# SparkFun_Dev_ESP32_C3_MINI.net
KiCad netlist of a schematic drawn in EAGLE
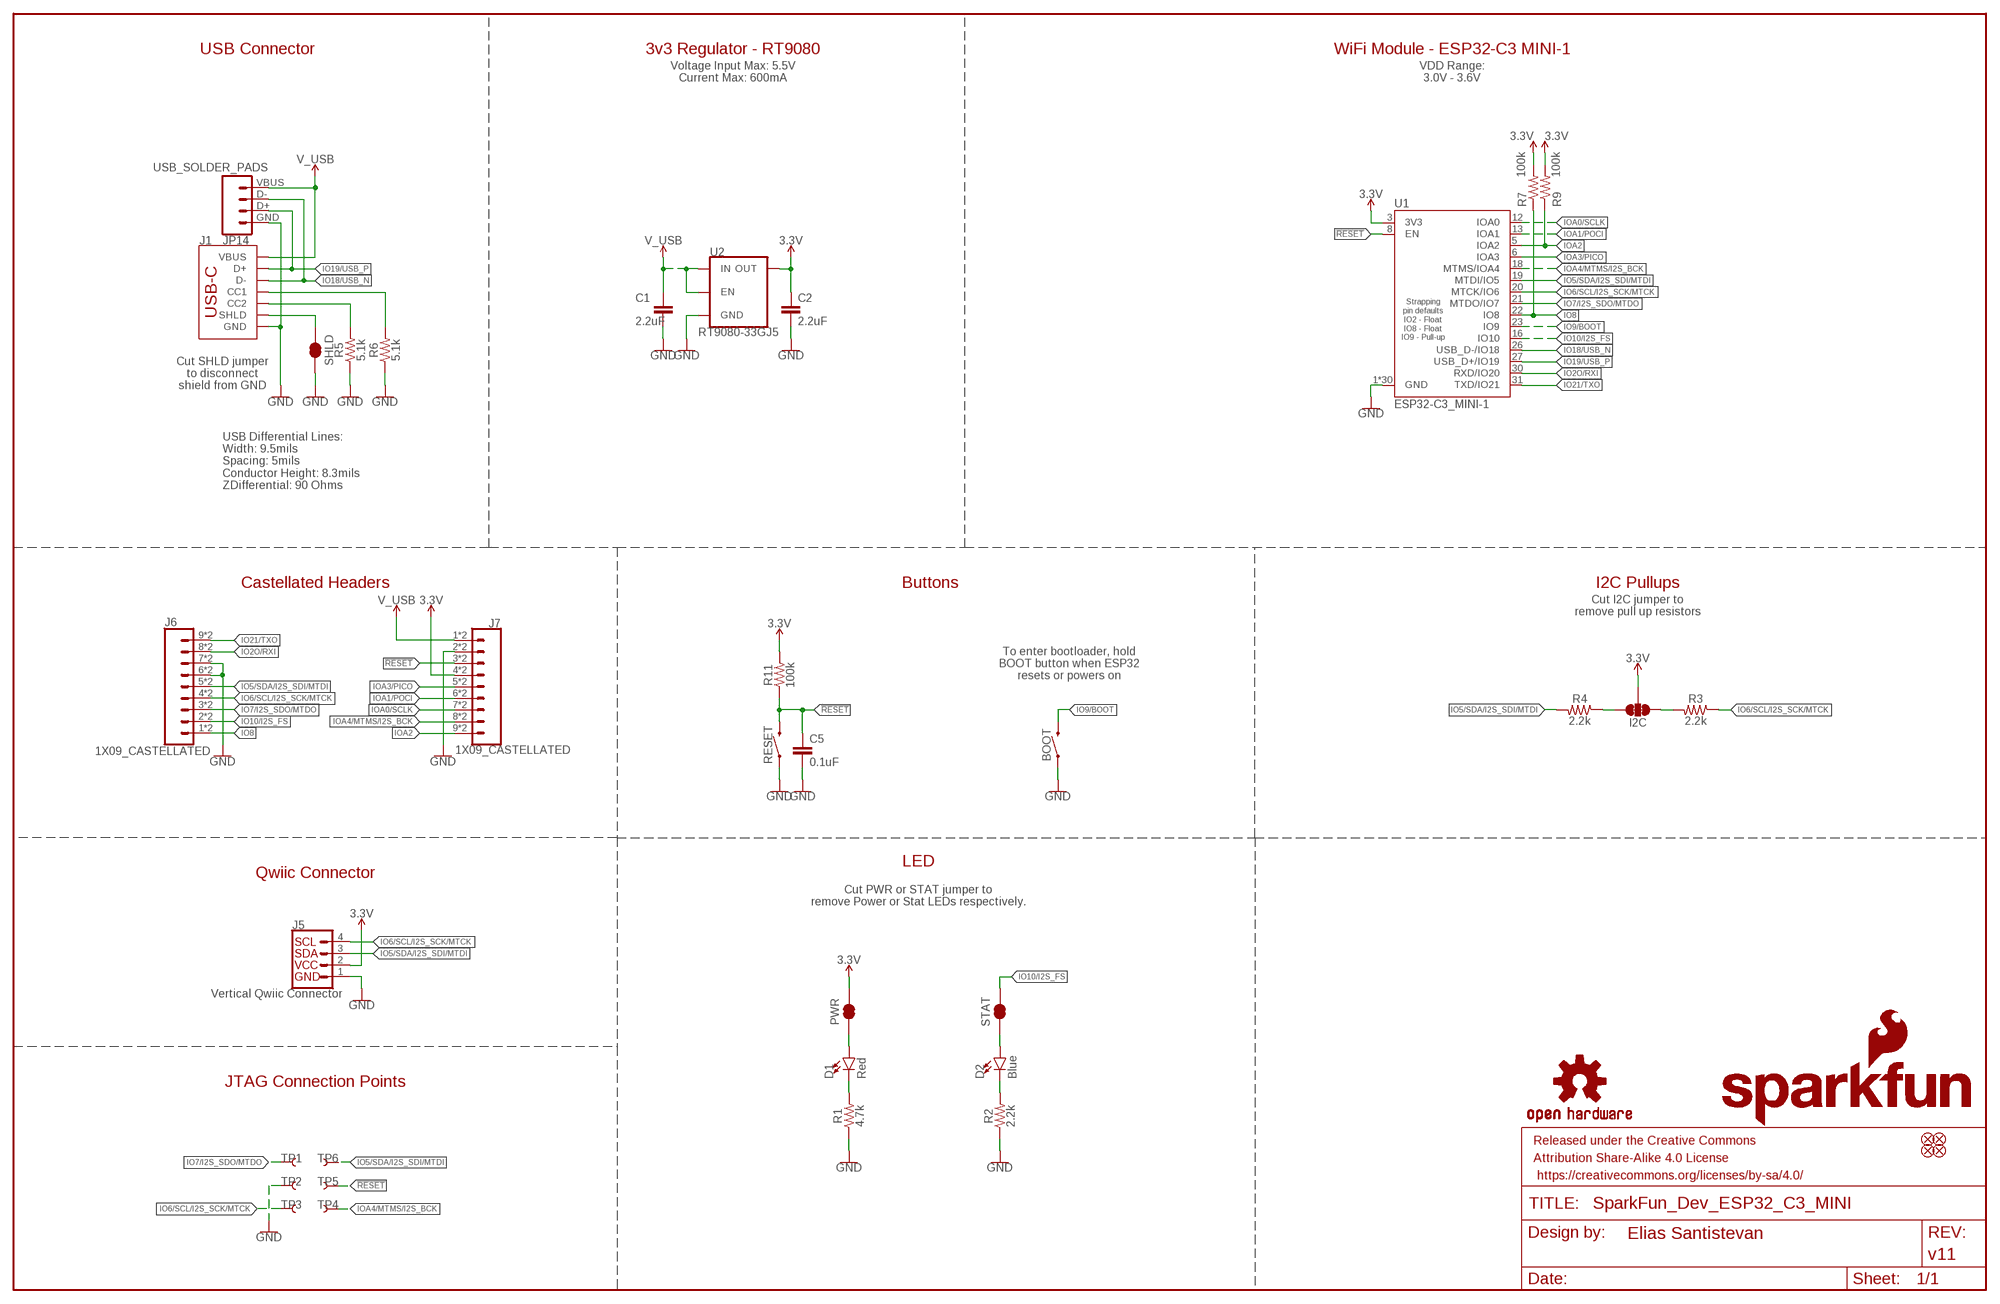
[diagram p0: schematic, sheet 1]

(export (version "E")
  (design (tool "Eeschema 10.0.6"))
  (components
    (comp (ref "BOOT")
      (value "MOMENTARY-SWITCH-SPST-SMD-4.6X2.8MM")
      (footprint "eagle-import:TACTILE_SWITCH_SMD_4.6X2.8MM")
      (libsource (lib "eagle-import") (part "MOMENTARY-SWITCH-SPST-SMD-4.6X2.8MM"))
    )
    (comp (ref "C1")
      (value "2.2uF")
      (footprint "eagle-import:0402-TIGHT")
      (libsource (lib "eagle-import") (part "2.2UF-0402_TIGHT-10V-10%-X5R"))
    )
    (comp (ref "C2")
      (value "2.2uF")
      (footprint "eagle-import:0402-TIGHT")
      (libsource (lib "eagle-import") (part "2.2UF-0402_TIGHT-10V-10%-X5R"))
    )
    (comp (ref "C5")
      (value "0.1uF")
      (footprint "eagle-import:0402-TIGHT")
      (libsource (lib "eagle-import") (part "0.1UF-0402T-6.3V-10%-X7R"))
    )
    (comp (ref "D1")
      (value "Red")
      (footprint "eagle-import:LED-0603")
      (libsource (lib "eagle-import") (part "LED-RED_0603-KB"))
    )
    (comp (ref "D2")
      (value "Blue")
      (footprint "eagle-import:LED-0603")
      (libsource (lib "eagle-import") (part "LED-BLUE0603"))
    )
    (comp (ref "FD1")
      (value "FIDUCIALUFIDUCIAL")
      (footprint "eagle-import:FIDUCIAL-MICRO")
      (libsource (lib "eagle-import") (part "FIDUCIALUFIDUCIAL"))
    )
    (comp (ref "FD2")
      (value "FIDUCIALUFIDUCIAL")
      (footprint "eagle-import:FIDUCIAL-MICRO")
      (libsource (lib "eagle-import") (part "FIDUCIALUFIDUCIAL"))
    )
    (comp (ref "FD3")
      (value "FIDUCIALUFIDUCIAL")
      (footprint "eagle-import:FIDUCIAL-MICRO")
      (libsource (lib "eagle-import") (part "FIDUCIALUFIDUCIAL"))
    )
    (comp (ref "FD4")
      (value "FIDUCIALUFIDUCIAL")
      (footprint "eagle-import:FIDUCIAL-MICRO")
      (libsource (lib "eagle-import") (part "FIDUCIALUFIDUCIAL"))
    )
    (comp (ref "FRAME2")
      (value "FRAME-LEDGER")
      (footprint "eagle-import:CREATIVE_COMMONS")
      (fields (field (name "DESIGNER") "Elias Santistevan") (field (name "REV") "v11"))
      (libsource (lib "eagle-import") (part "FRAME-LEDGER"))
    )
    (comp (ref "I2C")
      (value "JUMPER-SMT_3_2-NC_TRACE_SILK")
      (footprint "eagle-import:SMT-JUMPER_3_2-NC_TRACE_SILK")
      (libsource (lib "eagle-import") (part "JUMPER-SMT_3_2-NC_TRACE_SILK"))
    )
    (comp (ref "J1")
      (value "USB Female Type C Connector")
      (footprint "eagle-import:USB-C-16P_4LAYER-PADS")
      (libsource (lib "eagle-import") (part "USB_C_4-LAYER_PADS"))
    )
    (comp (ref "J5")
      (value "Vertical Qwiic Connector")
      (footprint "eagle-import:JST04_1MM_VERT")
      (libsource (lib "eagle-import") (part "QWIIC_CONNECTOR"))
    )
    (comp (ref "J6")
      (value "1X09_CASTELLATED")
      (footprint "eagle-import:1X09_CASTELLATED")
      (libsource (lib "eagle-import") (part "1X09_CASTELLATED"))
    )
    (comp (ref "J7")
      (value "1X09_CASTELLATED")
      (footprint "eagle-import:1X09_CASTELLATED")
      (libsource (lib "eagle-import") (part "1X09_CASTELLATED"))
    )
    (comp (ref "JP14")
      (value "USB_SOLDER_PADS")
      (footprint "eagle-import:USB-SOLDER-PADS")
      (libsource (lib "eagle-import") (part "USB_SOLDER_PADS"))
    )
    (comp (ref "LOGO1")
      (value "SFE_LOGO_NAME_FLAMEBLANK")
      (footprint "eagle-import:BLANK")
      (libsource (lib "eagle-import") (part "SFE_LOGO_NAME_FLAMEBLANK"))
    )
    (comp (ref "LOGO3")
      (value "OSHW-LOGOS")
      (footprint "eagle-import:OSHW-LOGO-S")
      (libsource (lib "eagle-import") (part "OSHW-LOGOS"))
    )
    (comp (ref "PWR")
      (value "JUMPER-SMT_2_NC_TRACE_SILK")
      (footprint "eagle-import:SMT-JUMPER_2_NC_TRACE_SILK")
      (libsource (lib "eagle-import") (part "JUMPER-SMT_2_NC_TRACE_SILK"))
    )
    (comp (ref "R1")
      (value "4.7k")
      (footprint "eagle-import:0402-TIGHT")
      (libsource (lib "eagle-import") (part "4.7KOHM-0402T-1/16W-1%"))
    )
    (comp (ref "R2")
      (value "2.2k")
      (footprint "eagle-import:0402-TIGHT")
      (libsource (lib "eagle-import") (part "2.2KOHM-0402T-1/16W-1%"))
    )
    (comp (ref "R3")
      (value "2.2k")
      (footprint "eagle-import:0402-TIGHT")
      (libsource (lib "eagle-import") (part "2.2KOHM-0402T-1/16W-1%"))
    )
    (comp (ref "R4")
      (value "2.2k")
      (footprint "eagle-import:0402-TIGHT")
      (libsource (lib "eagle-import") (part "2.2KOHM-0402T-1/16W-1%"))
    )
    (comp (ref "R5")
      (value "5.1k")
      (footprint "eagle-import:0402-TIGHT")
      (libsource (lib "eagle-import") (part "5.1KOHM-0402T-1/16W-1%"))
    )
    (comp (ref "R6")
      (value "5.1k")
      (footprint "eagle-import:0402-TIGHT")
      (libsource (lib "eagle-import") (part "5.1KOHM-0402T-1/16W-1%"))
    )
    (comp (ref "R7")
      (value "100k")
      (footprint "eagle-import:0402-TIGHT")
      (libsource (lib "eagle-import") (part "100KOHM-0402T-1/16W-1%"))
    )
    (comp (ref "R9")
      (value "100k")
      (footprint "eagle-import:0402-TIGHT")
      (libsource (lib "eagle-import") (part "100KOHM-0402T-1/16W-1%"))
    )
    (comp (ref "R11")
      (value "100k")
      (footprint "eagle-import:0402-TIGHT")
      (libsource (lib "eagle-import") (part "100KOHM-0402T-1/16W-1%"))
    )
    (comp (ref "RESET")
      (value "MOMENTARY-SWITCH-SPST-SMD-4.6X2.8MM")
      (footprint "eagle-import:TACTILE_SWITCH_SMD_4.6X2.8MM")
      (libsource (lib "eagle-import") (part "MOMENTARY-SWITCH-SPST-SMD-4.6X2.8MM"))
    )
    (comp (ref "SHLD")
      (value "JUMPER-SMT_2_NC_TRACE_SILK")
      (footprint "eagle-import:SMT-JUMPER_2_NC_TRACE_SILK")
      (libsource (lib "eagle-import") (part "JUMPER-SMT_2_NC_TRACE_SILK"))
    )
    (comp (ref "STAT")
      (value "JUMPER-SMT_2_NC_TRACE_SILK")
      (footprint "eagle-import:SMT-JUMPER_2_NC_TRACE_SILK")
      (libsource (lib "eagle-import") (part "JUMPER-SMT_2_NC_TRACE_SILK"))
    )
    (comp (ref "TP1")
      (value "TEST-POINT3X5")
      (footprint "eagle-import:PAD.03X.05")
      (libsource (lib "eagle-import") (part "TEST-POINT3X5"))
    )
    (comp (ref "TP2")
      (value "TEST-POINT3X5")
      (footprint "eagle-import:PAD.03X.05")
      (libsource (lib "eagle-import") (part "TEST-POINT3X5"))
    )
    (comp (ref "TP3")
      (value "TEST-POINT3X5")
      (footprint "eagle-import:PAD.03X.05")
      (libsource (lib "eagle-import") (part "TEST-POINT3X5"))
    )
    (comp (ref "TP4")
      (value "TEST-POINT3X5")
      (footprint "eagle-import:PAD.03X.05")
      (libsource (lib "eagle-import") (part "TEST-POINT3X5"))
    )
    (comp (ref "TP5")
      (value "TEST-POINT3X5")
      (footprint "eagle-import:PAD.03X.05")
      (libsource (lib "eagle-import") (part "TEST-POINT3X5"))
    )
    (comp (ref "TP6")
      (value "TEST-POINT3X5")
      (footprint "eagle-import:PAD.03X.05")
      (libsource (lib "eagle-import") (part "TEST-POINT3X5"))
    )
    (comp (ref "U1")
      (value "ESP32-C3_MINI-1")
      (footprint "eagle-import:ESP32-C3-MINI-1")
      (libsource (lib "eagle-import") (part "ESP32-C3_MINI-1"))
    )
    (comp (ref "U2")
      (value "RT9080-33GJ5")
      (footprint "eagle-import:SOT23-5")
      (libsource (lib "eagle-import") (part "V_REG_RT9080"))
    )
  )
  (nets
    (net (code "1") (name "/~{RESET}") (class "Default")
      (node (ref "C5") (pin "1") (pinfunction "1_1") (pintype "passive"))
      (node (ref "J7") (pin "3") (pinfunction "3_3") (pintype "passive"))
      (node (ref "J7") (pin "3B") (pinfunction "3_3B") (pintype "passive"))
      (node (ref "R11") (pin "1") (pinfunction "1_1") (pintype "passive"))
      (node (ref "RESET") (pin "3") (pinfunction "2_3") (pintype "passive"))
      (node (ref "RESET") (pin "4") (pinfunction "2_4") (pintype "passive"))
      (node (ref "TP5") (pin "1") (pinfunction "1_1") (pintype "bidirectional"))
      (node (ref "U1") (pin "8") (pinfunction "EN_8") (pintype "bidirectional"))
    )
    (net (code "2") (name "3.3V") (class "Default")
      (node (ref "C2") (pin "1") (pinfunction "1_1") (pintype "passive"))
      (node (ref "I2C") (pin "2") (pinfunction "2_2") (pintype "passive"))
      (node (ref "J5") (pin "2") (pinfunction "2_2") (pintype "power_in"))
      (node (ref "J7") (pin "4") (pinfunction "4_4") (pintype "passive"))
      (node (ref "J7") (pin "4B") (pinfunction "4_4B") (pintype "passive"))
      (node (ref "PWR") (pin "2") (pinfunction "2_2") (pintype "passive"))
      (node (ref "R11") (pin "2") (pinfunction "2_2") (pintype "passive"))
      (node (ref "R7") (pin "2") (pinfunction "2_2") (pintype "passive"))
      (node (ref "R9") (pin "2") (pinfunction "2_2") (pintype "passive"))
      (node (ref "U1") (pin "3") (pinfunction "3V3_3") (pintype "bidirectional"))
      (node (ref "U2") (pin "5") (pinfunction "OUT_5") (pintype "passive"))
    )
    (net (code "3") (name "GND") (class "Default")
      (node (ref "BOOT") (pin "1") (pinfunction "1_1") (pintype "passive"))
      (node (ref "BOOT") (pin "2") (pinfunction "1_2") (pintype "passive"))
      (node (ref "C1") (pin "2") (pinfunction "2_2") (pintype "passive"))
      (node (ref "C2") (pin "2") (pinfunction "2_2") (pintype "passive"))
      (node (ref "C5") (pin "2") (pinfunction "2_2") (pintype "passive"))
      (node (ref "J1") (pin "GND") (pinfunction "GND_GND") (pintype "bidirectional"))
      (node (ref "J1") (pin "GND2") (pinfunction "GND_GND2") (pintype "bidirectional"))
      (node (ref "J5") (pin "1") (pinfunction "1_1") (pintype "power_in"))
      (node (ref "J6") (pin "6") (pinfunction "6_6") (pintype "passive"))
      (node (ref "J6") (pin "6B") (pinfunction "6_6B") (pintype "passive"))
      (node (ref "J6") (pin "7") (pinfunction "7_7") (pintype "passive"))
      (node (ref "J6") (pin "7B") (pinfunction "7_7B") (pintype "passive"))
      (node (ref "J7") (pin "2") (pinfunction "2_2") (pintype "passive"))
      (node (ref "J7") (pin "2B") (pinfunction "2_2B") (pintype "passive"))
      (node (ref "JP14") (pin "GND") (pinfunction "4_GND") (pintype "passive"))
      (node (ref "R1") (pin "1") (pinfunction "1_1") (pintype "passive"))
      (node (ref "R2") (pin "1") (pinfunction "1_1") (pintype "passive"))
      (node (ref "R5") (pin "1") (pinfunction "1_1") (pintype "passive"))
      (node (ref "R6") (pin "1") (pinfunction "1_1") (pintype "passive"))
      (node (ref "RESET") (pin "1") (pinfunction "1_1") (pintype "passive"))
      (node (ref "RESET") (pin "2") (pinfunction "1_2") (pintype "passive"))
      (node (ref "SHLD") (pin "2") (pinfunction "2_2") (pintype "passive"))
      (node (ref "TP2") (pin "1") (pinfunction "1_1") (pintype "bidirectional"))
      (node (ref "U1") (pin "1") (pinfunction "GND_1") (pintype "bidirectional"))
      (node (ref "U1") (pin "11") (pinfunction "GND_11") (pintype "bidirectional"))
      (node (ref "U1") (pin "14") (pinfunction "GND_14") (pintype "bidirectional"))
      (node (ref "U1") (pin "2") (pinfunction "GND_2") (pintype "bidirectional"))
      (node (ref "U1") (pin "36") (pinfunction "GND_36") (pintype "bidirectional"))
      (node (ref "U1") (pin "37") (pinfunction "GND_37") (pintype "bidirectional"))
      (node (ref "U1") (pin "38") (pinfunction "GND_38") (pintype "bidirectional"))
      (node (ref "U1") (pin "39") (pinfunction "GND_39") (pintype "bidirectional"))
      (node (ref "U1") (pin "40") (pinfunction "GND_40") (pintype "bidirectional"))
      (node (ref "U1") (pin "41") (pinfunction "GND_41") (pintype "bidirectional"))
      (node (ref "U1") (pin "42") (pinfunction "GND_42") (pintype "bidirectional"))
      (node (ref "U1") (pin "43") (pinfunction "GND_43") (pintype "bidirectional"))
      (node (ref "U1") (pin "44") (pinfunction "GND_44") (pintype "bidirectional"))
      (node (ref "U1") (pin "45") (pinfunction "GND_45") (pintype "bidirectional"))
      (node (ref "U1") (pin "46") (pinfunction "GND_46") (pintype "bidirectional"))
      (node (ref "U1") (pin "47") (pinfunction "GND_47") (pintype "bidirectional"))
      (node (ref "U1") (pin "48") (pinfunction "GND_48") (pintype "bidirectional"))
      (node (ref "U1") (pin "49.1") (pinfunction "GND_49.1") (pintype "bidirectional"))
      (node (ref "U1") (pin "49.2") (pinfunction "GND_49.2") (pintype "bidirectional"))
      (node (ref "U1") (pin "49.3") (pinfunction "GND_49.3") (pintype "bidirectional"))
      (node (ref "U1") (pin "49.4") (pinfunction "GND_49.4") (pintype "bidirectional"))
      (node (ref "U1") (pin "49.5") (pinfunction "GND_49.5") (pintype "bidirectional"))
      (node (ref "U1") (pin "49.6") (pinfunction "GND_49.6") (pintype "bidirectional"))
      (node (ref "U1") (pin "49.7") (pinfunction "GND_49.7") (pintype "bidirectional"))
      (node (ref "U1") (pin "49.8") (pinfunction "GND_49.8") (pintype "bidirectional"))
      (node (ref "U1") (pin "49.9") (pinfunction "GND_49.9") (pintype "bidirectional"))
      (node (ref "U1") (pin "50") (pinfunction "GND_50") (pintype "bidirectional"))
      (node (ref "U1") (pin "51") (pinfunction "GND_51") (pintype "bidirectional"))
      (node (ref "U1") (pin "52") (pinfunction "GND_52") (pintype "bidirectional"))
      (node (ref "U1") (pin "53") (pinfunction "GND_53") (pintype "bidirectional"))
      (node (ref "U2") (pin "2") (pinfunction "GND_2") (pintype "input"))
    )
    (net (code "4") (name "IO2O{slash}RXI") (class "Default")
      (node (ref "J6") (pin "8") (pinfunction "8_8") (pintype "passive"))
      (node (ref "J6") (pin "8B") (pinfunction "8_8B") (pintype "passive"))
      (node (ref "U1") (pin "30") (pinfunction "RXD/IO20_30") (pintype "bidirectional"))
    )
    (net (code "5") (name "IO5{slash}SDA{slash}I2S_SDI{slash}MTDI") (class "Default")
      (node (ref "J5") (pin "3") (pinfunction "3_3") (pintype "passive"))
      (node (ref "J6") (pin "5") (pinfunction "5_5") (pintype "passive"))
      (node (ref "J6") (pin "5B") (pinfunction "5_5B") (pintype "passive"))
      (node (ref "R4") (pin "2") (pinfunction "2_2") (pintype "passive"))
      (node (ref "TP6") (pin "1") (pinfunction "1_1") (pintype "bidirectional"))
      (node (ref "U1") (pin "19") (pinfunction "MTDI/IO5_19") (pintype "bidirectional"))
    )
    (net (code "6") (name "IO6{slash}SCL{slash}I2S_SCK{slash}MTCK") (class "Default")
      (node (ref "J5") (pin "4") (pinfunction "4_4") (pintype "passive"))
      (node (ref "J6") (pin "4") (pinfunction "4_4") (pintype "passive"))
      (node (ref "J6") (pin "4B") (pinfunction "4_4B") (pintype "passive"))
      (node (ref "R3") (pin "1") (pinfunction "1_1") (pintype "passive"))
      (node (ref "TP3") (pin "1") (pinfunction "1_1") (pintype "bidirectional"))
      (node (ref "U1") (pin "20") (pinfunction "MTCK/IO6_20") (pintype "bidirectional"))
    )
    (net (code "7") (name "IO7{slash}I2S_SDO{slash}MTDO") (class "Default")
      (node (ref "J6") (pin "3") (pinfunction "3_3") (pintype "passive"))
      (node (ref "J6") (pin "3B") (pinfunction "3_3B") (pintype "passive"))
      (node (ref "TP1") (pin "1") (pinfunction "1_1") (pintype "bidirectional"))
      (node (ref "U1") (pin "21") (pinfunction "MTDO/IO7_21") (pintype "bidirectional"))
    )
    (net (code "8") (name "IO8") (class "Default")
      (node (ref "J6") (pin "1") (pinfunction "1_1") (pintype "passive"))
      (node (ref "J6") (pin "1B") (pinfunction "1_1B") (pintype "passive"))
      (node (ref "R7") (pin "1") (pinfunction "1_1") (pintype "passive"))
      (node (ref "U1") (pin "22") (pinfunction "IO8_22") (pintype "bidirectional"))
    )
    (net (code "9") (name "IO9{slash}BOOT") (class "Default")
      (node (ref "BOOT") (pin "3") (pinfunction "2_3") (pintype "passive"))
      (node (ref "BOOT") (pin "4") (pinfunction "2_4") (pintype "passive"))
      (node (ref "U1") (pin "23") (pinfunction "IO9_23") (pintype "bidirectional"))
    )
    (net (code "10") (name "IO10{slash}I2S_FS") (class "Default")
      (node (ref "J6") (pin "2") (pinfunction "2_2") (pintype "passive"))
      (node (ref "J6") (pin "2B") (pinfunction "2_2B") (pintype "passive"))
      (node (ref "STAT") (pin "2") (pinfunction "2_2") (pintype "passive"))
      (node (ref "U1") (pin "16") (pinfunction "IO10_16") (pintype "bidirectional"))
    )
    (net (code "11") (name "IO18{slash}USB_N") (class "Default")
      (node (ref "J1") (pin "A7") (pinfunction "D-_A7") (pintype "bidirectional"))
      (node (ref "J1") (pin "B7") (pinfunction "D-_B7") (pintype "bidirectional"))
      (node (ref "JP14") (pin "D-") (pinfunction "2_D-") (pintype "passive"))
      (node (ref "U1") (pin "26") (pinfunction "USB_D-/IO18_26") (pintype "bidirectional"))
    )
    (net (code "12") (name "IO19{slash}USB_P") (class "Default")
      (node (ref "J1") (pin "A6") (pinfunction "D+_A6") (pintype "bidirectional"))
      (node (ref "J1") (pin "B6") (pinfunction "D+_B6") (pintype "bidirectional"))
      (node (ref "JP14") (pin "D+") (pinfunction "3_D+") (pintype "passive"))
      (node (ref "U1") (pin "27") (pinfunction "USB_D+/IO19_27") (pintype "bidirectional"))
    )
    (net (code "13") (name "IO21{slash}TXO") (class "Default")
      (node (ref "J6") (pin "9") (pinfunction "9_9") (pintype "passive"))
      (node (ref "J6") (pin "9B") (pinfunction "9_9B") (pintype "passive"))
      (node (ref "U1") (pin "31") (pinfunction "TXD/IO21_31") (pintype "bidirectional"))
    )
    (net (code "14") (name "IOA0{slash}SCLK") (class "Default")
      (node (ref "J7") (pin "7") (pinfunction "7_7") (pintype "passive"))
      (node (ref "J7") (pin "7B") (pinfunction "7_7B") (pintype "passive"))
      (node (ref "U1") (pin "12") (pinfunction "IOA0_12") (pintype "bidirectional"))
    )
    (net (code "15") (name "IOA1{slash}POCI") (class "Default")
      (node (ref "J7") (pin "6") (pinfunction "6_6") (pintype "passive"))
      (node (ref "J7") (pin "6B") (pinfunction "6_6B") (pintype "passive"))
      (node (ref "U1") (pin "13") (pinfunction "IOA1_13") (pintype "bidirectional"))
    )
    (net (code "16") (name "IOA2") (class "Default")
      (node (ref "J7") (pin "9") (pinfunction "9_9") (pintype "passive"))
      (node (ref "J7") (pin "9B") (pinfunction "9_9B") (pintype "passive"))
      (node (ref "R9") (pin "1") (pinfunction "1_1") (pintype "passive"))
      (node (ref "U1") (pin "5") (pinfunction "IOA2_5") (pintype "bidirectional"))
    )
    (net (code "17") (name "IOA3{slash}PICO") (class "Default")
      (node (ref "J7") (pin "5") (pinfunction "5_5") (pintype "passive"))
      (node (ref "J7") (pin "5B") (pinfunction "5_5B") (pintype "passive"))
      (node (ref "U1") (pin "6") (pinfunction "IOA3_6") (pintype "bidirectional"))
    )
    (net (code "18") (name "IOA4{slash}MTMS{slash}I2S_BCK") (class "Default")
      (node (ref "J7") (pin "8") (pinfunction "8_8") (pintype "passive"))
      (node (ref "J7") (pin "8B") (pinfunction "8_8B") (pintype "passive"))
      (node (ref "TP4") (pin "1") (pinfunction "1_1") (pintype "bidirectional"))
      (node (ref "U1") (pin "18") (pinfunction "MTMS/IOA4_18") (pintype "bidirectional"))
    )
    (net (code "19") (name "Net-(D1-PadA)") (class "Default")
      (node (ref "D1") (pin "A") (pinfunction "A_A") (pintype "passive"))
      (node (ref "PWR") (pin "1") (pinfunction "1_1") (pintype "passive"))
    )
    (net (code "20") (name "Net-(D1-PadC)") (class "Default")
      (node (ref "D1") (pin "C") (pinfunction "C_C") (pintype "passive"))
      (node (ref "R1") (pin "2") (pinfunction "2_2") (pintype "passive"))
    )
    (net (code "21") (name "Net-(D2-PadA)") (class "Default")
      (node (ref "D2") (pin "A") (pinfunction "A_A") (pintype "passive"))
      (node (ref "STAT") (pin "1") (pinfunction "1_1") (pintype "passive"))
    )
    (net (code "22") (name "Net-(D2-PadC)") (class "Default")
      (node (ref "D2") (pin "C") (pinfunction "C_C") (pintype "passive"))
      (node (ref "R2") (pin "2") (pinfunction "2_2") (pintype "passive"))
    )
    (net (code "23") (name "Net-(I2C-Pad1)") (class "Default")
      (node (ref "I2C") (pin "1") (pinfunction "1_1") (pintype "passive"))
      (node (ref "R4") (pin "1") (pinfunction "1_1") (pintype "passive"))
    )
    (net (code "24") (name "Net-(I2C-Pad3)") (class "Default")
      (node (ref "I2C") (pin "3") (pinfunction "3_3") (pintype "passive"))
      (node (ref "R3") (pin "2") (pinfunction "2_2") (pintype "passive"))
    )
    (net (code "25") (name "Net-(J1-CC1)") (class "Default")
      (node (ref "J1") (pin "A5") (pinfunction "CC1_A5") (pintype "bidirectional"))
      (node (ref "R6") (pin "2") (pinfunction "2_2") (pintype "passive"))
    )
    (net (code "26") (name "Net-(J1-CC2)") (class "Default")
      (node (ref "J1") (pin "B5") (pinfunction "CC2_B5") (pintype "bidirectional"))
      (node (ref "R5") (pin "2") (pinfunction "2_2") (pintype "passive"))
    )
    (net (code "27") (name "Net-(J1-SHLD-PadSHLD1)") (class "Default")
      (node (ref "J1") (pin "SHLD1") (pinfunction "SHLD_SHLD1") (pintype "bidirectional"))
      (node (ref "J1") (pin "SHLD2") (pinfunction "SHLD_SHLD2") (pintype "bidirectional"))
      (node (ref "J1") (pin "SHLD3") (pinfunction "SHLD_SHLD3") (pintype "bidirectional"))
      (node (ref "J1") (pin "SHLD4") (pinfunction "SHLD_SHLD4") (pintype "bidirectional"))
      (node (ref "SHLD") (pin "1") (pinfunction "1_1") (pintype "passive"))
    )
    (net (code "28") (name "V_USB") (class "Default")
      (node (ref "C1") (pin "1") (pinfunction "1_1") (pintype "passive"))
      (node (ref "J1") (pin "VBUS1") (pinfunction "VBUS_VBUS1") (pintype "bidirectional"))
      (node (ref "J1") (pin "VBUS2") (pinfunction "VBUS_VBUS2") (pintype "bidirectional"))
      (node (ref "J7") (pin "1") (pinfunction "1_1") (pintype "passive"))
      (node (ref "J7") (pin "1B") (pinfunction "1_1B") (pintype "passive"))
      (node (ref "JP14") (pin "VBUS") (pinfunction "1_VBUS") (pintype "passive"))
      (node (ref "U2") (pin "1") (pinfunction "IN_1") (pintype "input"))
      (node (ref "U2") (pin "3") (pinfunction "EN_3") (pintype "input"))
    )
  )
)
